# WeMos32Proto.net
KiCad netlist of a schematic drawn in EAGLE
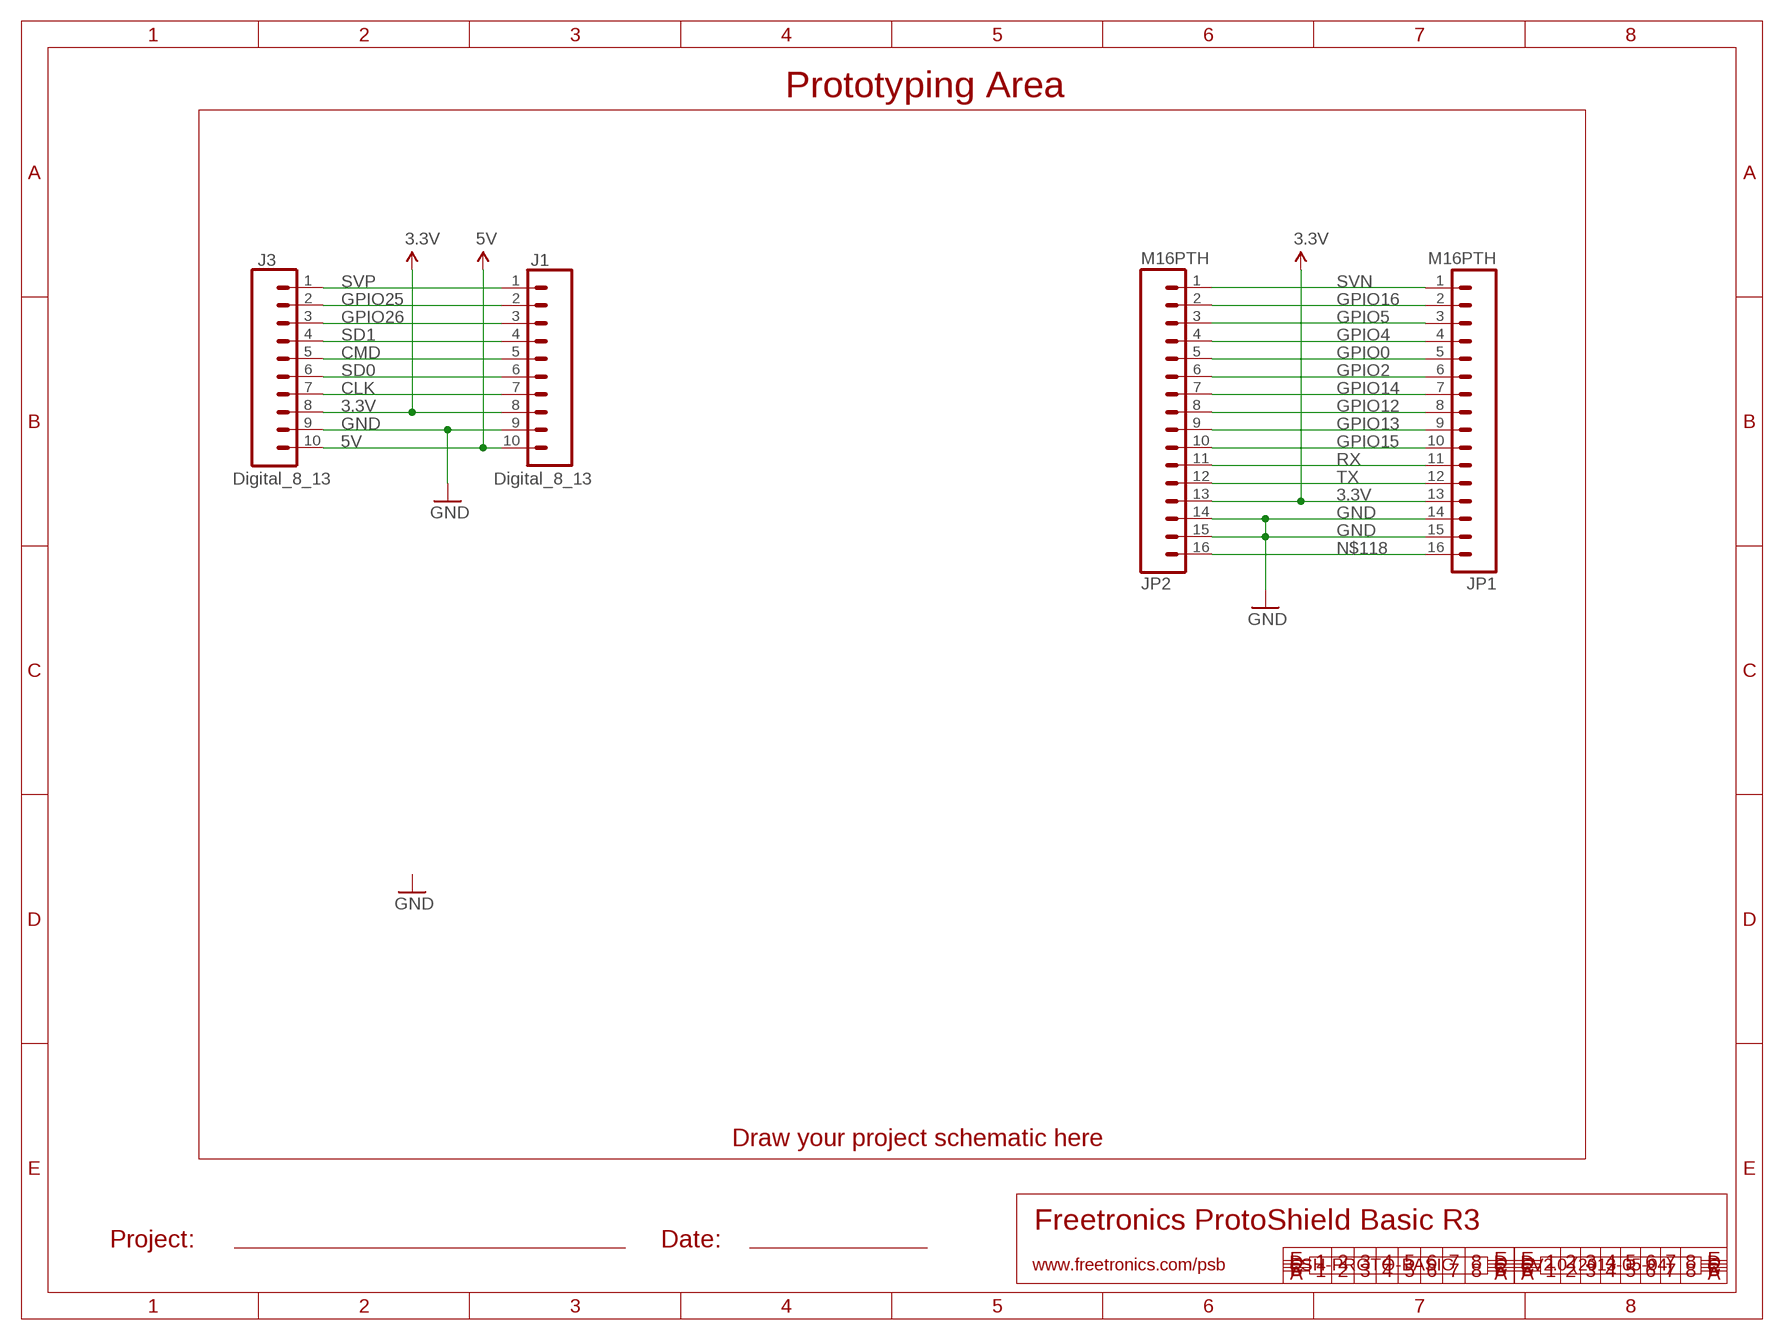
[diagram p0: schematic, sheet 1]

(export (version "E")
  (design (tool "Eeschema 10.0.6"))
  (components
    (comp (ref "J1")
      (value "Digital_8_13")
      (footprint "eagle-import:1X10")
      (libsource (lib "eagle-import") (part "M100.1"))
    )
    (comp (ref "J3")
      (value "Digital_8_13")
      (footprint "eagle-import:1X10")
      (libsource (lib "eagle-import") (part "M100.1"))
    )
    (comp (ref "JP1")
      (value "M16PTH")
      (footprint "eagle-import:1X16")
      (libsource (lib "eagle-import") (part "M16PTH"))
    )
    (comp (ref "JP2")
      (value "M16PTH")
      (footprint "eagle-import:1X16")
      (libsource (lib "eagle-import") (part "M16PTH"))
    )
  )
  (nets
    (net (code "1") (name "/CLK") (class "Default")
      (node (ref "J1") (pin "7") (pinfunction "7_7") (pintype "passive"))
      (node (ref "J3") (pin "7") (pinfunction "7_7") (pintype "passive"))
    )
    (net (code "2") (name "/CMD") (class "Default")
      (node (ref "J1") (pin "5") (pinfunction "5_5") (pintype "passive"))
      (node (ref "J3") (pin "5") (pinfunction "5_5") (pintype "passive"))
    )
    (net (code "3") (name "/GPIO0") (class "Default")
      (node (ref "JP1") (pin "5") (pinfunction "5_5") (pintype "passive"))
      (node (ref "JP2") (pin "5") (pinfunction "5_5") (pintype "passive"))
    )
    (net (code "4") (name "/GPIO2") (class "Default")
      (node (ref "JP1") (pin "6") (pinfunction "6_6") (pintype "passive"))
      (node (ref "JP2") (pin "6") (pinfunction "6_6") (pintype "passive"))
    )
    (net (code "5") (name "/GPIO4") (class "Default")
      (node (ref "JP1") (pin "4") (pinfunction "4_4") (pintype "passive"))
      (node (ref "JP2") (pin "4") (pinfunction "4_4") (pintype "passive"))
    )
    (net (code "6") (name "/GPIO5") (class "Default")
      (node (ref "JP1") (pin "3") (pinfunction "3_3") (pintype "passive"))
      (node (ref "JP2") (pin "3") (pinfunction "3_3") (pintype "passive"))
    )
    (net (code "7") (name "/GPIO12") (class "Default")
      (node (ref "JP1") (pin "8") (pinfunction "8_8") (pintype "passive"))
      (node (ref "JP2") (pin "8") (pinfunction "8_8") (pintype "passive"))
    )
    (net (code "8") (name "/GPIO13") (class "Default")
      (node (ref "JP1") (pin "9") (pinfunction "9_9") (pintype "passive"))
      (node (ref "JP2") (pin "9") (pinfunction "9_9") (pintype "passive"))
    )
    (net (code "9") (name "/GPIO14") (class "Default")
      (node (ref "JP1") (pin "7") (pinfunction "7_7") (pintype "passive"))
      (node (ref "JP2") (pin "7") (pinfunction "7_7") (pintype "passive"))
    )
    (net (code "10") (name "/GPIO15") (class "Default")
      (node (ref "JP1") (pin "10") (pinfunction "10_10") (pintype "passive"))
      (node (ref "JP2") (pin "10") (pinfunction "10_10") (pintype "passive"))
    )
    (net (code "11") (name "/GPIO16") (class "Default")
      (node (ref "JP1") (pin "2") (pinfunction "2_2") (pintype "passive"))
      (node (ref "JP2") (pin "2") (pinfunction "2_2") (pintype "passive"))
    )
    (net (code "12") (name "/GPIO25") (class "Default")
      (node (ref "J1") (pin "2") (pinfunction "2_2") (pintype "passive"))
      (node (ref "J3") (pin "2") (pinfunction "2_2") (pintype "passive"))
    )
    (net (code "13") (name "/GPIO26") (class "Default")
      (node (ref "J1") (pin "3") (pinfunction "3_3") (pintype "passive"))
      (node (ref "J3") (pin "3") (pinfunction "3_3") (pintype "passive"))
    )
    (net (code "14") (name "/N$118") (class "Default")
      (node (ref "JP1") (pin "16") (pinfunction "16_16") (pintype "passive"))
      (node (ref "JP2") (pin "16") (pinfunction "16_16") (pintype "passive"))
    )
    (net (code "15") (name "/RX") (class "Default")
      (node (ref "JP1") (pin "11") (pinfunction "11_11") (pintype "passive"))
      (node (ref "JP2") (pin "11") (pinfunction "11_11") (pintype "passive"))
    )
    (net (code "16") (name "/SD0") (class "Default")
      (node (ref "J1") (pin "6") (pinfunction "6_6") (pintype "passive"))
      (node (ref "J3") (pin "6") (pinfunction "6_6") (pintype "passive"))
    )
    (net (code "17") (name "/SD1") (class "Default")
      (node (ref "J1") (pin "4") (pinfunction "4_4") (pintype "passive"))
      (node (ref "J3") (pin "4") (pinfunction "4_4") (pintype "passive"))
    )
    (net (code "18") (name "/SVN") (class "Default")
      (node (ref "JP1") (pin "1") (pinfunction "1_1") (pintype "passive"))
      (node (ref "JP2") (pin "1") (pinfunction "1_1") (pintype "passive"))
    )
    (net (code "19") (name "/SVP") (class "Default")
      (node (ref "J1") (pin "1") (pinfunction "1_1") (pintype "passive"))
      (node (ref "J3") (pin "1") (pinfunction "1_1") (pintype "passive"))
    )
    (net (code "20") (name "/TX") (class "Default")
      (node (ref "JP1") (pin "12") (pinfunction "12_12") (pintype "passive"))
      (node (ref "JP2") (pin "12") (pinfunction "12_12") (pintype "passive"))
    )
    (net (code "21") (name "3.3V") (class "Default")
      (node (ref "J1") (pin "8") (pinfunction "8_8") (pintype "passive"))
      (node (ref "J3") (pin "8") (pinfunction "8_8") (pintype "passive"))
      (node (ref "JP1") (pin "13") (pinfunction "13_13") (pintype "passive"))
      (node (ref "JP2") (pin "13") (pinfunction "13_13") (pintype "passive"))
    )
    (net (code "22") (name "5V") (class "Default")
      (node (ref "J1") (pin "10") (pinfunction "10_10") (pintype "passive"))
      (node (ref "J3") (pin "10") (pinfunction "10_10") (pintype "passive"))
    )
    (net (code "23") (name "GND") (class "Default")
      (node (ref "J1") (pin "9") (pinfunction "9_9") (pintype "passive"))
      (node (ref "J3") (pin "9") (pinfunction "9_9") (pintype "passive"))
      (node (ref "JP1") (pin "14") (pinfunction "14_14") (pintype "passive"))
      (node (ref "JP1") (pin "15") (pinfunction "15_15") (pintype "passive"))
      (node (ref "JP2") (pin "14") (pinfunction "14_14") (pintype "passive"))
      (node (ref "JP2") (pin "15") (pinfunction "15_15") (pintype "passive"))
    )
  )
)
